# Kasli-SOC_power-controller.net
KiCad netlist of a schematic drawn in Altium Designer
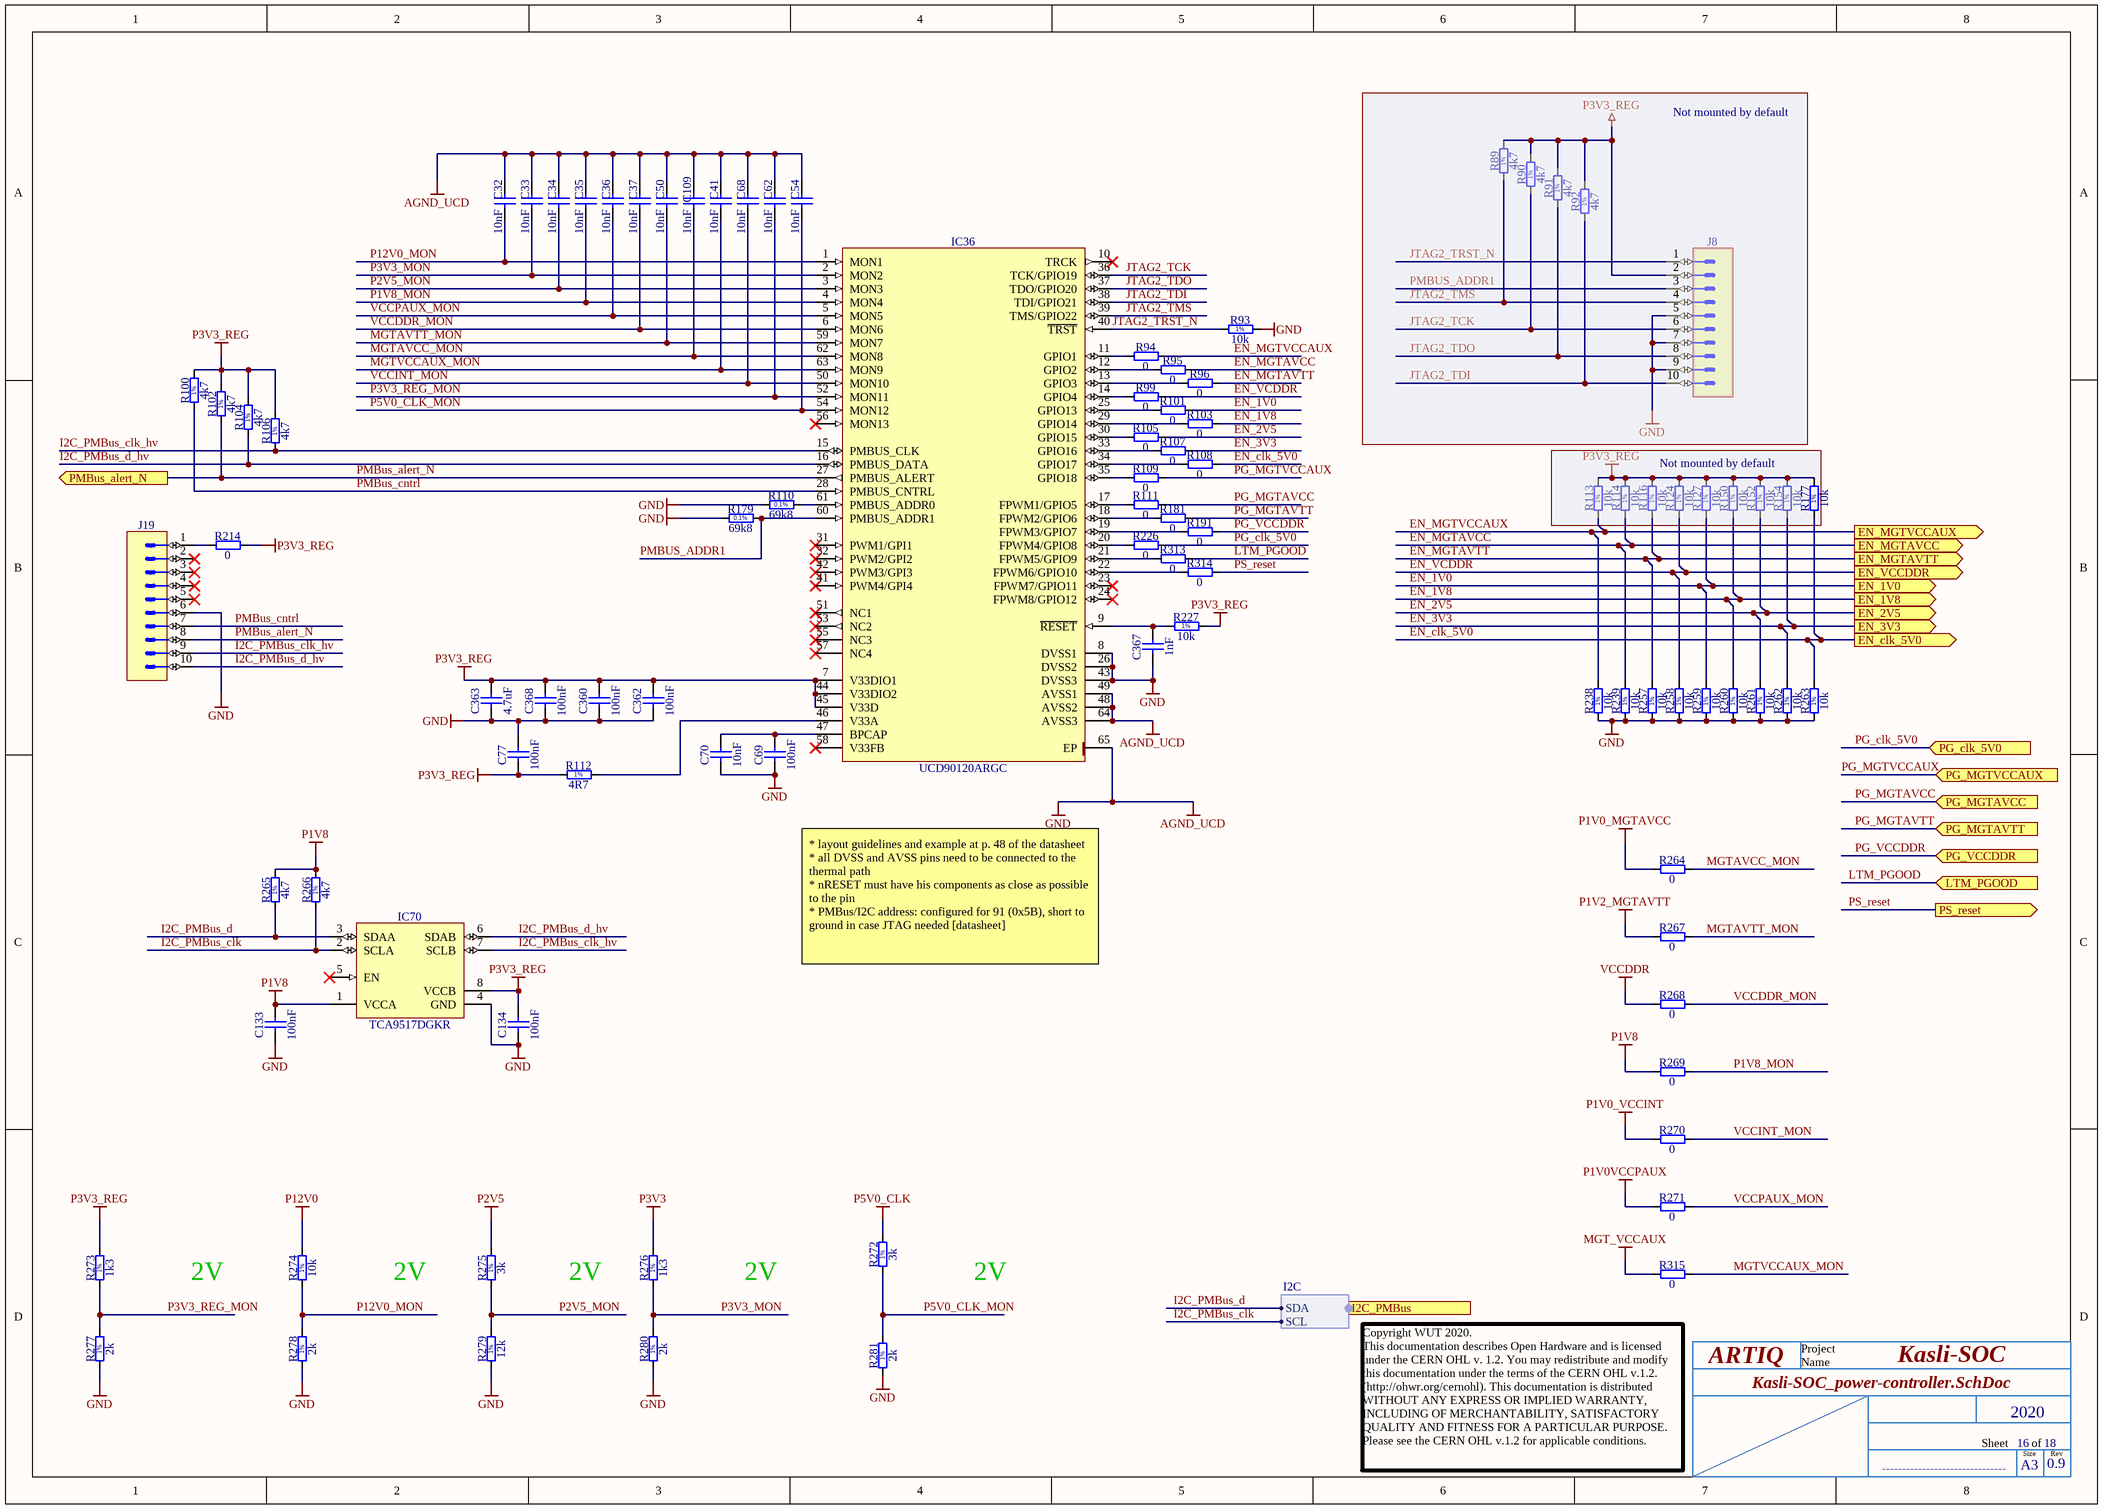
[diagram p0: Kasli-SOC_power-controller.SchDoc]

(export (version "E")
  (design (tool "Eeschema 10.0.6"))
  (components
    (comp (ref "C32")
      (value "10nF")
      (footprint "CAPC1005X55N")
      (description "Non-polarised capacitor")
      (fields (field (name "PART NUMBER") "CC0402_10NF_25V_10%_X7R") (field (name "VOLTAGE") "25V"))
      (libsource (lib "Capacitors") (part "Capacitor - non polarized"))
    )
    (comp (ref "C33")
      (value "10nF")
      (footprint "CAPC1005X55N")
      (description "Non-polarised capacitor")
      (fields (field (name "PART NUMBER") "CC0402_10NF_25V_10%_X7R") (field (name "VOLTAGE") "25V"))
      (libsource (lib "Capacitors") (part "Capacitor - non polarized"))
    )
    (comp (ref "C34")
      (value "10nF")
      (footprint "CAPC1005X55N")
      (description "Non-polarised capacitor")
      (fields (field (name "PART NUMBER") "CC0402_10NF_25V_10%_X7R") (field (name "VOLTAGE") "25V"))
      (libsource (lib "Capacitors") (part "Capacitor - non polarized"))
    )
    (comp (ref "C35")
      (value "10nF")
      (footprint "CAPC1005X55N")
      (description "Non-polarised capacitor")
      (fields (field (name "PART NUMBER") "CC0402_10NF_25V_10%_X7R") (field (name "VOLTAGE") "25V"))
      (libsource (lib "Capacitors") (part "Capacitor - non polarized"))
    )
    (comp (ref "C36")
      (value "10nF")
      (footprint "CAPC1005X55N")
      (description "Non-polarised capacitor")
      (fields (field (name "PART NUMBER") "CC0402_10NF_25V_10%_X7R") (field (name "VOLTAGE") "25V"))
      (libsource (lib "Capacitors") (part "Capacitor - non polarized"))
    )
    (comp (ref "C37")
      (value "10nF")
      (footprint "CAPC1005X55N")
      (description "Non-polarised capacitor")
      (fields (field (name "PART NUMBER") "CC0402_10NF_25V_10%_X7R") (field (name "VOLTAGE") "25V"))
      (libsource (lib "Capacitors") (part "Capacitor - non polarized"))
    )
    (comp (ref "C41")
      (value "10nF")
      (footprint "CAPC1005X55N")
      (description "Non-polarised capacitor")
      (fields (field (name "PART NUMBER") "CC0402_10NF_25V_10%_X7R") (field (name "VOLTAGE") "25V"))
      (libsource (lib "Capacitors") (part "Capacitor - non polarized"))
    )
    (comp (ref "C50")
      (value "10nF")
      (footprint "CAPC1005X55N")
      (description "Non-polarised capacitor")
      (fields (field (name "PART NUMBER") "CC0402_10NF_25V_10%_X7R") (field (name "VOLTAGE") "25V"))
      (libsource (lib "Capacitors") (part "Capacitor - non polarized"))
    )
    (comp (ref "C54")
      (value "10nF")
      (footprint "CAPC1005X55N")
      (description "Non-polarised capacitor")
      (fields (field (name "PART NUMBER") "CC0402_10NF_25V_10%_X7R") (field (name "VOLTAGE") "25V"))
      (libsource (lib "Capacitors") (part "Capacitor - non polarized"))
    )
    (comp (ref "C62")
      (value "10nF")
      (footprint "CAPC1005X55N")
      (description "Non-polarised capacitor")
      (fields (field (name "PART NUMBER") "CC0402_10NF_25V_10%_X7R") (field (name "VOLTAGE") "25V"))
      (libsource (lib "Capacitors") (part "Capacitor - non polarized"))
    )
    (comp (ref "C68")
      (value "10nF")
      (footprint "CAPC1005X55N")
      (description "Non-polarised capacitor")
      (fields (field (name "PART NUMBER") "CC0402_10NF_25V_10%_X7R") (field (name "VOLTAGE") "25V"))
      (libsource (lib "Capacitors") (part "Capacitor - non polarized"))
    )
    (comp (ref "C69")
      (value "100nF")
      (footprint "CAPC1005X55N")
      (description "Non-polarised capacitor")
      (fields (field (name "PART NUMBER") "CC0402_100NF_16V_10%_X7R") (field (name "VOLTAGE") "16V"))
      (libsource (lib "Capacitors") (part "Capacitor - non polarized"))
    )
    (comp (ref "C70")
      (value "10nF")
      (footprint "CAPC1005X55N")
      (description "Non-polarised capacitor")
      (fields (field (name "PART NUMBER") "CC0402_10NF_25V_10%_X7R") (field (name "VOLTAGE") "25V"))
      (libsource (lib "Capacitors") (part "Capacitor - non polarized"))
    )
    (comp (ref "C77")
      (value "100nF")
      (footprint "CAPC1005X55N")
      (description "Non-polarised capacitor")
      (fields (field (name "PART NUMBER") "CC0402_100NF_16V_10%_X7R") (field (name "VOLTAGE") "16V"))
      (libsource (lib "Capacitors") (part "Capacitor - non polarized"))
    )
    (comp (ref "C109")
      (value "10nF")
      (footprint "CAPC1005X55N")
      (description "Non-polarised capacitor")
      (fields (field (name "PART NUMBER") "CC0402_10NF_25V_10%_X7R") (field (name "VOLTAGE") "25V"))
      (libsource (lib "Capacitors") (part "Capacitor - non polarized"))
    )
    (comp (ref "C133")
      (value "100nF")
      (footprint "CAPC1005X55N")
      (description "Non-polarised capacitor")
      (fields (field (name "PART NUMBER") "CC0402_100NF_16V_10%_X7R") (field (name "VOLTAGE") "16V"))
      (libsource (lib "Capacitors") (part "Capacitor - non polarized"))
    )
    (comp (ref "C134")
      (value "100nF")
      (footprint "CAPC1005X55N")
      (description "Non-polarised capacitor")
      (fields (field (name "PART NUMBER") "CC0402_100NF_16V_10%_X7R") (field (name "VOLTAGE") "16V"))
      (libsource (lib "Capacitors") (part "Capacitor - non polarized"))
    )
    (comp (ref "C360")
      (value "100nF")
      (footprint "CAPC1005X55N")
      (description "Non-polarised capacitor")
      (fields (field (name "PART NUMBER") "CC0402_100NF_16V_10%_X7R") (field (name "VOLTAGE") "16V"))
      (libsource (lib "Capacitors") (part "Capacitor - non polarized"))
    )
    (comp (ref "C362")
      (value "100nF")
      (footprint "CAPC1005X55N")
      (description "Non-polarised capacitor")
      (fields (field (name "PART NUMBER") "CC0402_100NF_16V_10%_X7R") (field (name "VOLTAGE") "16V"))
      (libsource (lib "Capacitors") (part "Capacitor - non polarized"))
    )
    (comp (ref "C363")
      (value "4.7uF")
      (footprint "CAPC1005X55N")
      (description "Non-polarised capacitor")
      (fields (field (name "PART NUMBER") "CC0402_4.7UF_6.3V_20%_X5R") (field (name "VOLTAGE") "6.3V"))
      (libsource (lib "Capacitors") (part "Capacitor - non polarized"))
    )
    (comp (ref "C367")
      (value "1nF")
      (footprint "CAPC1005X55N")
      (description "Non-polarised capacitor")
      (fields (field (name "PART NUMBER") "CC0402_1NF_50V_10%_X7R") (field (name "VOLTAGE") "50V"))
      (libsource (lib "Capacitors") (part "Capacitor - non polarized"))
    )
    (comp (ref "C368")
      (value "100nF")
      (footprint "CAPC1005X55N")
      (description "Non-polarised capacitor")
      (fields (field (name "PART NUMBER") "CC0402_100NF_16V_10%_X7R") (field (name "VOLTAGE") "16V"))
      (libsource (lib "Capacitors") (part "Capacitor - non polarized"))
    )
    (comp (ref "IC36")
      (value "UCD90120ARGC")
      (footprint "QFN50P900X900X100-65N-S425")
      (description "12-Rail Power Supply Sequencer and Monitor")
      (fields (field (name "MANUFACTURER") "TEXAS INSTRUMENTS"))
      (libsource (lib "ICs And Semiconductors") (part "UCD90120ARGC"))
    )
    (comp (ref "IC70")
      (value "TCA9517DGKR")
      (footprint "SOP65P490X110-8N")
      (description "Level-Translating I2C Bus Repeater")
      (fields (field (name "MANUFACTURER") "TEXAS INSTRUMENTS"))
      (libsource (lib "ICs And Semiconductors") (part "TCA9517"))
    )
    (comp (ref "J8")
      (value "AMPMODU")
      (footprint "TYCO_1241050-5")
      (description "Connector 10 Male")
      (fields (field (name "PART NUMBER") "TYCO_1241050-5") (field (name "MANUFACTURER") "TYCO ELECTRONICS"))
      (libsource (lib "Connectors") (part "Connector 10 Male"))
    )
    (comp (ref "J19")
      (value "AMPMODU")
      (footprint "TYCO_1241050-5")
      (description "Connector 10 Male")
      (fields (field (name "PART NUMBER") "TYCO_1241050-5") (field (name "MANUFACTURER") "TYCO ELECTRONICS"))
      (libsource (lib "") (part "Connector 10 Male_1"))
    )
    (comp (ref "R89")
      (value "4k7")
      (footprint "RESC1005X40N")
      (description "Resistor - 1%")
      (fields (field (name "PART NUMBER") "R0402_4K7_1%_0.0625W_100PPM") (field (name "POWER") "0.0625W"))
      (libsource (lib "Resistors") (part "Resistor - 1%"))
    )
    (comp (ref "R90")
      (value "4k7")
      (footprint "RESC1005X40N")
      (description "Resistor - 1%")
      (fields (field (name "PART NUMBER") "R0402_4K7_1%_0.0625W_100PPM") (field (name "POWER") "0.0625W"))
      (libsource (lib "Resistors") (part "Resistor - 1%"))
    )
    (comp (ref "R91")
      (value "4k7")
      (footprint "RESC1005X40N")
      (description "Resistor - 1%")
      (fields (field (name "PART NUMBER") "R0402_4K7_1%_0.0625W_100PPM") (field (name "POWER") "0.0625W"))
      (libsource (lib "Resistors") (part "Resistor - 1%"))
    )
    (comp (ref "R92")
      (value "4k7")
      (footprint "RESC1005X40N")
      (description "Resistor - 1%")
      (fields (field (name "PART NUMBER") "R0402_4K7_1%_0.0625W_100PPM") (field (name "POWER") "0.0625W"))
      (libsource (lib "Resistors") (part "Resistor - 1%"))
    )
    (comp (ref "R93")
      (value "10k")
      (footprint "RESC1005X40N")
      (description "Resistor - 1%")
      (fields (field (name "PART NUMBER") "R0402_10K_1%_0.0625W_100PPM") (field (name "POWER") "0.0625W"))
      (libsource (lib "Resistors") (part "Resistor - 1%"))
    )
    (comp (ref "R94")
      (value "0")
      (footprint "RESC1005X40N")
      (description "Resistor")
      (fields (field (name "PART NUMBER") "R0402_0R_JUMPER") (field (name "MANUFACTURER") "GENERIC"))
      (libsource (lib "Resistors") (part "Resistor"))
    )
    (comp (ref "R95")
      (value "0")
      (footprint "RESC1005X40N")
      (description "Resistor")
      (fields (field (name "PART NUMBER") "R0402_0R_JUMPER") (field (name "MANUFACTURER") "GENERIC"))
      (libsource (lib "Resistors") (part "Resistor"))
    )
    (comp (ref "R96")
      (value "0")
      (footprint "RESC1005X40N")
      (description "Resistor")
      (fields (field (name "PART NUMBER") "R0402_0R_JUMPER") (field (name "MANUFACTURER") "GENERIC"))
      (libsource (lib "Resistors") (part "Resistor"))
    )
    (comp (ref "R99")
      (value "0")
      (footprint "RESC1005X40N")
      (description "Resistor")
      (fields (field (name "PART NUMBER") "R0402_0R_JUMPER") (field (name "MANUFACTURER") "GENERIC"))
      (libsource (lib "Resistors") (part "Resistor"))
    )
    (comp (ref "R100")
      (value "4k7")
      (footprint "RESC1005X40N")
      (description "Resistor - 1%")
      (fields (field (name "PART NUMBER") "R0402_4K7_1%_0.0625W_100PPM") (field (name "POWER") "0.0625W"))
      (libsource (lib "Resistors") (part "Resistor - 1%"))
    )
    (comp (ref "R101")
      (value "0")
      (footprint "RESC1005X40N")
      (description "Resistor")
      (fields (field (name "PART NUMBER") "R0402_0R_JUMPER") (field (name "MANUFACTURER") "GENERIC"))
      (libsource (lib "Resistors") (part "Resistor"))
    )
    (comp (ref "R102")
      (value "4k7")
      (footprint "RESC1005X40N")
      (description "Resistor - 1%")
      (fields (field (name "PART NUMBER") "R0402_4K7_1%_0.0625W_100PPM") (field (name "POWER") "0.0625W"))
      (libsource (lib "Resistors") (part "Resistor - 1%"))
    )
    (comp (ref "R103")
      (value "0")
      (footprint "RESC1005X40N")
      (description "Resistor")
      (fields (field (name "PART NUMBER") "R0402_0R_JUMPER") (field (name "MANUFACTURER") "GENERIC"))
      (libsource (lib "Resistors") (part "Resistor"))
    )
    (comp (ref "R104")
      (value "4k7")
      (footprint "RESC1005X40N")
      (description "Resistor - 1%")
      (fields (field (name "PART NUMBER") "R0402_4K7_1%_0.0625W_100PPM") (field (name "POWER") "0.0625W"))
      (libsource (lib "Resistors") (part "Resistor - 1%"))
    )
    (comp (ref "R105")
      (value "0")
      (footprint "RESC1005X40N")
      (description "Resistor")
      (fields (field (name "PART NUMBER") "R0402_0R_JUMPER") (field (name "MANUFACTURER") "GENERIC"))
      (libsource (lib "Resistors") (part "Resistor"))
    )
    (comp (ref "R106")
      (value "4k7")
      (footprint "RESC1005X40N")
      (description "Resistor - 1%")
      (fields (field (name "PART NUMBER") "R0402_4K7_1%_0.0625W_100PPM") (field (name "POWER") "0.0625W"))
      (libsource (lib "Resistors") (part "Resistor - 1%"))
    )
    (comp (ref "R107")
      (value "0")
      (footprint "RESC1005X40N")
      (description "Resistor")
      (fields (field (name "PART NUMBER") "R0402_0R_JUMPER") (field (name "MANUFACTURER") "GENERIC"))
      (libsource (lib "Resistors") (part "Resistor"))
    )
    (comp (ref "R108")
      (value "0")
      (footprint "RESC1005X40N")
      (description "Resistor")
      (fields (field (name "PART NUMBER") "R0402_0R_JUMPER") (field (name "MANUFACTURER") "GENERIC"))
      (libsource (lib "Resistors") (part "Resistor"))
    )
    (comp (ref "R109")
      (value "0")
      (footprint "RESC1005X40N")
      (description "Resistor")
      (fields (field (name "PART NUMBER") "R0402_0R_JUMPER") (field (name "MANUFACTURER") "GENERIC"))
      (libsource (lib "Resistors") (part "Resistor"))
    )
    (comp (ref "R110")
      (value "69k8")
      (footprint "RESC1608X55N")
      (description "Resistor - 0.1%")
      (fields (field (name "PART NUMBER") "R0603_69K8_0.1%_0.063W_10PPM") (field (name "POWER") "0.063W"))
      (libsource (lib "Resistors") (part "Resistor - 0.1%"))
    )
    (comp (ref "R111")
      (value "0")
      (footprint "RESC1005X40N")
      (description "Resistor")
      (fields (field (name "PART NUMBER") "R0402_0R_JUMPER") (field (name "MANUFACTURER") "GENERIC"))
      (libsource (lib "Resistors") (part "Resistor"))
    )
    (comp (ref "R112")
      (value "4R7")
      (footprint "RESC2012X60N")
      (description "Resistor - 1%")
      (fields (field (name "PART NUMBER") "R0805_4R7_1%_0.125W_200PPM") (field (name "POWER") "0.125W"))
      (libsource (lib "Resistors") (part "Resistor - 1%"))
    )
    (comp (ref "R113")
      (value "10k")
      (footprint "RESC1005X40N")
      (description "Resistor - 1%")
      (fields (field (name "PART NUMBER") "R0402_10K_1%_0.0625W_100PPM") (field (name "POWER") "0.0625W"))
      (libsource (lib "Resistors") (part "Resistor - 1%"))
    )
    (comp (ref "R114")
      (value "10k")
      (footprint "RESC1005X40N")
      (description "Resistor - 1%")
      (fields (field (name "PART NUMBER") "R0402_10K_1%_0.0625W_100PPM") (field (name "POWER") "0.0625W"))
      (libsource (lib "Resistors") (part "Resistor - 1%"))
    )
    (comp (ref "R116")
      (value "10k")
      (footprint "RESC1005X40N")
      (description "Resistor - 1%")
      (fields (field (name "PART NUMBER") "R0402_10K_1%_0.0625W_100PPM") (field (name "POWER") "0.0625W"))
      (libsource (lib "Resistors") (part "Resistor - 1%"))
    )
    (comp (ref "R124")
      (value "10k")
      (footprint "RESC1005X40N")
      (description "Resistor - 1%")
      (fields (field (name "PART NUMBER") "R0402_10K_1%_0.0625W_100PPM") (field (name "POWER") "0.0625W"))
      (libsource (lib "Resistors") (part "Resistor - 1%"))
    )
    (comp (ref "R127")
      (value "10k")
      (footprint "RESC1005X40N")
      (description "Resistor - 1%")
      (fields (field (name "PART NUMBER") "R0402_10K_1%_0.0625W_100PPM") (field (name "POWER") "0.0625W"))
      (libsource (lib "Resistors") (part "Resistor - 1%"))
    )
    (comp (ref "R150")
      (value "10k")
      (footprint "RESC1005X40N")
      (description "Resistor - 1%")
      (fields (field (name "PART NUMBER") "R0402_10K_1%_0.0625W_100PPM") (field (name "POWER") "0.0625W"))
      (libsource (lib "Resistors") (part "Resistor - 1%"))
    )
    (comp (ref "R152")
      (value "10k")
      (footprint "RESC1005X40N")
      (description "Resistor - 1%")
      (fields (field (name "PART NUMBER") "R0402_10K_1%_0.0625W_100PPM") (field (name "POWER") "0.0625W"))
      (libsource (lib "Resistors") (part "Resistor - 1%"))
    )
    (comp (ref "R154")
      (value "10k")
      (footprint "RESC1005X40N")
      (description "Resistor - 1%")
      (fields (field (name "PART NUMBER") "R0402_10K_1%_0.0625W_100PPM") (field (name "POWER") "0.0625W"))
      (libsource (lib "Resistors") (part "Resistor - 1%"))
    )
    (comp (ref "R177")
      (value "10k")
      (footprint "RESC1005X40N")
      (description "Resistor - 1%")
      (fields (field (name "PART NUMBER") "R0402_10K_1%_0.0625W_100PPM") (field (name "POWER") "0.0625W"))
      (libsource (lib "Resistors") (part "Resistor - 1%"))
    )
    (comp (ref "R179")
      (value "69k8")
      (footprint "RESC1608X55N")
      (description "Resistor - 0.1%")
      (fields (field (name "PART NUMBER") "R0603_69K8_0.1%_0.063W_10PPM") (field (name "POWER") "0.063W"))
      (libsource (lib "Resistors") (part "Resistor - 0.1%"))
    )
    (comp (ref "R181")
      (value "0")
      (footprint "RESC1005X40N")
      (description "Resistor")
      (fields (field (name "PART NUMBER") "R0402_0R_JUMPER") (field (name "MANUFACTURER") "GENERIC"))
      (libsource (lib "Resistors") (part "Resistor"))
    )
    (comp (ref "R191")
      (value "0")
      (footprint "RESC1005X40N")
      (description "Resistor")
      (fields (field (name "PART NUMBER") "R0402_0R_JUMPER") (field (name "MANUFACTURER") "GENERIC"))
      (libsource (lib "Resistors") (part "Resistor"))
    )
    (comp (ref "R214")
      (value "0")
      (footprint "RESC1005X40N")
      (description "Resistor")
      (fields (field (name "PART NUMBER") "R0402_0R_JUMPER") (field (name "MANUFACTURER") "GENERIC"))
      (libsource (lib "Resistors") (part "Resistor"))
    )
    (comp (ref "R226")
      (value "0")
      (footprint "RESC1005X40N")
      (description "Resistor")
      (fields (field (name "PART NUMBER") "R0402_0R_JUMPER") (field (name "MANUFACTURER") "GENERIC"))
      (libsource (lib "Resistors") (part "Resistor"))
    )
    (comp (ref "R227")
      (value "10k")
      (footprint "RESC1005X40N")
      (description "Resistor - 1%")
      (fields (field (name "PART NUMBER") "R0402_10K_1%_0.0625W_100PPM") (field (name "POWER") "0.0625W"))
      (libsource (lib "Resistors") (part "Resistor - 1%"))
    )
    (comp (ref "R238")
      (value "10k")
      (footprint "RESC1005X40N")
      (description "Resistor - 1%")
      (fields (field (name "PART NUMBER") "R0402_10K_1%_0.0625W_100PPM") (field (name "POWER") "0.0625W"))
      (libsource (lib "Resistors") (part "Resistor - 1%"))
    )
    (comp (ref "R239")
      (value "10k")
      (footprint "RESC1005X40N")
      (description "Resistor - 1%")
      (fields (field (name "PART NUMBER") "R0402_10K_1%_0.0625W_100PPM") (field (name "POWER") "0.0625W"))
      (libsource (lib "Resistors") (part "Resistor - 1%"))
    )
    (comp (ref "R257")
      (value "10k")
      (footprint "RESC1005X40N")
      (description "Resistor - 1%")
      (fields (field (name "PART NUMBER") "R0402_10K_1%_0.0625W_100PPM") (field (name "POWER") "0.0625W"))
      (libsource (lib "Resistors") (part "Resistor - 1%"))
    )
    (comp (ref "R258")
      (value "10k")
      (footprint "RESC1005X40N")
      (description "Resistor - 1%")
      (fields (field (name "PART NUMBER") "R0402_10K_1%_0.0625W_100PPM") (field (name "POWER") "0.0625W"))
      (libsource (lib "Resistors") (part "Resistor - 1%"))
    )
    (comp (ref "R259")
      (value "10k")
      (footprint "RESC1005X40N")
      (description "Resistor - 1%")
      (fields (field (name "PART NUMBER") "R0402_10K_1%_0.0625W_100PPM") (field (name "POWER") "0.0625W"))
      (libsource (lib "Resistors") (part "Resistor - 1%"))
    )
    (comp (ref "R260")
      (value "10k")
      (footprint "RESC1005X40N")
      (description "Resistor - 1%")
      (fields (field (name "PART NUMBER") "R0402_10K_1%_0.0625W_100PPM") (field (name "POWER") "0.0625W"))
      (libsource (lib "Resistors") (part "Resistor - 1%"))
    )
    (comp (ref "R261")
      (value "10k")
      (footprint "RESC1005X40N")
      (description "Resistor - 1%")
      (fields (field (name "PART NUMBER") "R0402_10K_1%_0.0625W_100PPM") (field (name "POWER") "0.0625W"))
      (libsource (lib "Resistors") (part "Resistor - 1%"))
    )
    (comp (ref "R262")
      (value "10k")
      (footprint "RESC1005X40N")
      (description "Resistor - 1%")
      (fields (field (name "PART NUMBER") "R0402_10K_1%_0.0625W_100PPM") (field (name "POWER") "0.0625W"))
      (libsource (lib "Resistors") (part "Resistor - 1%"))
    )
    (comp (ref "R263")
      (value "10k")
      (footprint "RESC1005X40N")
      (description "Resistor - 1%")
      (fields (field (name "PART NUMBER") "R0402_10K_1%_0.0625W_100PPM") (field (name "POWER") "0.0625W"))
      (libsource (lib "Resistors") (part "Resistor - 1%"))
    )
    (comp (ref "R264")
      (value "0")
      (footprint "RESC1005X40N")
      (description "Resistor")
      (fields (field (name "PART NUMBER") "R0402_0R_JUMPER") (field (name "MANUFACTURER") "GENERIC"))
      (libsource (lib "Resistors") (part "Resistor"))
    )
    (comp (ref "R265")
      (value "4k7")
      (footprint "RESC2012X60N")
      (description "Resistor - 1%")
      (fields (field (name "PART NUMBER") "R0805_4K7_1%_0.125W_100PPM") (field (name "POWER") "0.125W"))
      (libsource (lib "Resistors") (part "Resistor - 1%"))
    )
    (comp (ref "R266")
      (value "4k7")
      (footprint "RESC2012X60N")
      (description "Resistor - 1%")
      (fields (field (name "PART NUMBER") "R0805_4K7_1%_0.125W_100PPM") (field (name "POWER") "0.125W"))
      (libsource (lib "Resistors") (part "Resistor - 1%"))
    )
    (comp (ref "R267")
      (value "0")
      (footprint "RESC1005X40N")
      (description "Resistor")
      (fields (field (name "PART NUMBER") "R0402_0R_JUMPER") (field (name "MANUFACTURER") "GENERIC"))
      (libsource (lib "Resistors") (part "Resistor"))
    )
    (comp (ref "R268")
      (value "0")
      (footprint "RESC1005X40N")
      (description "Resistor")
      (fields (field (name "PART NUMBER") "R0402_0R_JUMPER") (field (name "MANUFACTURER") "GENERIC"))
      (libsource (lib "Resistors") (part "Resistor"))
    )
    (comp (ref "R269")
      (value "0")
      (footprint "RESC1005X40N")
      (description "Resistor")
      (fields (field (name "PART NUMBER") "R0402_0R_JUMPER") (field (name "MANUFACTURER") "GENERIC"))
      (libsource (lib "Resistors") (part "Resistor"))
    )
    (comp (ref "R270")
      (value "0")
      (footprint "RESC1005X40N")
      (description "Resistor")
      (fields (field (name "PART NUMBER") "R0402_0R_JUMPER") (field (name "MANUFACTURER") "GENERIC"))
      (libsource (lib "Resistors") (part "Resistor"))
    )
    (comp (ref "R271")
      (value "0")
      (footprint "RESC1005X40N")
      (description "Resistor")
      (fields (field (name "PART NUMBER") "R0402_0R_JUMPER") (field (name "MANUFACTURER") "GENERIC"))
      (libsource (lib "Resistors") (part "Resistor"))
    )
    (comp (ref "R272")
      (value "3k")
      (footprint "RESC1005X40N")
      (description "Resistor - 1%")
      (fields (field (name "PART NUMBER") "R0402_3K_1%_0.0625W_100PPM") (field (name "POWER") "0.0625W"))
      (libsource (lib "Resistors") (part "Resistor - 1%"))
    )
    (comp (ref "R273")
      (value "1k3")
      (footprint "RESC1005X40N")
      (description "Resistor - 1%")
      (fields (field (name "PART NUMBER") "R0402_1K3_1%_0.0625W_100PPM") (field (name "POWER") "0.0625W"))
      (libsource (lib "Resistors") (part "Resistor - 1%"))
    )
    (comp (ref "R274")
      (value "10k")
      (footprint "RESC1005X40N")
      (description "Resistor - 1%")
      (fields (field (name "PART NUMBER") "R0402_10K_1%_0.0625W_100PPM") (field (name "POWER") "0.0625W"))
      (libsource (lib "Resistors") (part "Resistor - 1%"))
    )
    (comp (ref "R275")
      (value "3k")
      (footprint "RESC1005X40N")
      (description "Resistor - 1%")
      (fields (field (name "PART NUMBER") "R0402_3K_1%_0.0625W_100PPM") (field (name "POWER") "0.0625W"))
      (libsource (lib "Resistors") (part "Resistor - 1%"))
    )
    (comp (ref "R276")
      (value "1k3")
      (footprint "RESC1005X40N")
      (description "Resistor - 1%")
      (fields (field (name "PART NUMBER") "R0402_1K3_1%_0.0625W_100PPM") (field (name "POWER") "0.0625W"))
      (libsource (lib "Resistors") (part "Resistor - 1%"))
    )
    (comp (ref "R277")
      (value "2k")
      (footprint "RESC1005X40N")
      (description "Resistor - 1%")
      (fields (field (name "PART NUMBER") "R0402_2K_1%_0.0625W_100PPM") (field (name "POWER") "0.0625W"))
      (libsource (lib "Resistors") (part "Resistor - 1%"))
    )
    (comp (ref "R278")
      (value "2k")
      (footprint "RESC1005X40N")
      (description "Resistor - 1%")
      (fields (field (name "PART NUMBER") "R0402_2K_1%_0.0625W_100PPM") (field (name "POWER") "0.0625W"))
      (libsource (lib "Resistors") (part "Resistor - 1%"))
    )
    (comp (ref "R279")
      (value "12k")
      (footprint "RESC1005X40N")
      (description "Resistor - 1%")
      (fields (field (name "PART NUMBER") "R0402_12K_1%_0.0625W_100PPM") (field (name "POWER") "0.0625W"))
      (libsource (lib "Resistors") (part "Resistor - 1%"))
    )
    (comp (ref "R280")
      (value "2k")
      (footprint "RESC1005X40N")
      (description "Resistor - 1%")
      (fields (field (name "PART NUMBER") "R0402_2K_1%_0.0625W_100PPM") (field (name "POWER") "0.0625W"))
      (libsource (lib "Resistors") (part "Resistor - 1%"))
    )
    (comp (ref "R281")
      (value "2k")
      (footprint "RESC1005X40N")
      (description "Resistor - 1%")
      (fields (field (name "PART NUMBER") "R0402_2K_1%_0.0625W_100PPM") (field (name "POWER") "0.0625W"))
      (libsource (lib "Resistors") (part "Resistor - 1%"))
    )
    (comp (ref "R313")
      (value "0")
      (footprint "RESC1005X40N")
      (description "Resistor")
      (fields (field (name "PART NUMBER") "R0402_0R_JUMPER") (field (name "MANUFACTURER") "GENERIC"))
      (libsource (lib "Resistors") (part "Resistor"))
    )
    (comp (ref "R314")
      (value "0")
      (footprint "RESC1005X40N")
      (description "Resistor")
      (fields (field (name "PART NUMBER") "R0402_0R_JUMPER") (field (name "MANUFACTURER") "GENERIC"))
      (libsource (lib "Resistors") (part "Resistor"))
    )
    (comp (ref "R315")
      (value "0")
      (footprint "RESC1005X40N")
      (description "Resistor")
      (fields (field (name "PART NUMBER") "R0402_0R_JUMPER") (field (name "MANUFACTURER") "GENERIC"))
      (libsource (lib "Resistors") (part "Resistor"))
    )
  )
  (nets
    (net (code "2") (name "/EN_1V0") (class "Default")
      (node (ref "R101") (pin "2") (pinfunction "2_2") (pintype "passive"))
      (node (ref "R127") (pin "1") (pinfunction "1_1") (pintype "passive"))
      (node (ref "R259") (pin "2") (pinfunction "2_2") (pintype "passive"))
    )
    (net (code "3") (name "/EN_1V8") (class "Default")
      (node (ref "R103") (pin "2") (pinfunction "2_2") (pintype "passive"))
      (node (ref "R150") (pin "1") (pinfunction "1_1") (pintype "passive"))
      (node (ref "R260") (pin "2") (pinfunction "2_2") (pintype "passive"))
    )
    (net (code "4") (name "/EN_2V5") (class "Default")
      (node (ref "R105") (pin "2") (pinfunction "2_2") (pintype "passive"))
      (node (ref "R152") (pin "1") (pinfunction "1_1") (pintype "passive"))
      (node (ref "R261") (pin "2") (pinfunction "2_2") (pintype "passive"))
    )
    (net (code "5") (name "/EN_3V3") (class "Default")
      (node (ref "R107") (pin "2") (pinfunction "2_2") (pintype "passive"))
      (node (ref "R154") (pin "1") (pinfunction "1_1") (pintype "passive"))
      (node (ref "R262") (pin "2") (pinfunction "2_2") (pintype "passive"))
    )
    (net (code "6") (name "/EN_MGTAVCC") (class "Default")
      (node (ref "R114") (pin "1") (pinfunction "1_1") (pintype "passive"))
      (node (ref "R239") (pin "2") (pinfunction "2_2") (pintype "passive"))
      (node (ref "R95") (pin "2") (pinfunction "2_2") (pintype "passive"))
    )
    (net (code "7") (name "/EN_MGTAVTT") (class "Default")
      (node (ref "R116") (pin "1") (pinfunction "1_1") (pintype "passive"))
      (node (ref "R257") (pin "2") (pinfunction "2_2") (pintype "passive"))
      (node (ref "R96") (pin "2") (pinfunction "2_2") (pintype "passive"))
    )
    (net (code "8") (name "/EN_MGTVCCAUX") (class "Default")
      (node (ref "R113") (pin "1") (pinfunction "1_1") (pintype "passive"))
      (node (ref "R238") (pin "2") (pinfunction "2_2") (pintype "passive"))
      (node (ref "R94") (pin "2") (pinfunction "2_2") (pintype "passive"))
    )
    (net (code "9") (name "/EN_VCDDR") (class "Default")
      (node (ref "R124") (pin "1") (pinfunction "1_1") (pintype "passive"))
      (node (ref "R258") (pin "2") (pinfunction "2_2") (pintype "passive"))
      (node (ref "R99") (pin "2") (pinfunction "2_2") (pintype "passive"))
    )
    (net (code "10") (name "/EN_clk_5V0") (class "Default")
      (node (ref "R108") (pin "2") (pinfunction "2_2") (pintype "passive"))
      (node (ref "R177") (pin "1") (pinfunction "1_1") (pintype "passive"))
      (node (ref "R263") (pin "2") (pinfunction "2_2") (pintype "passive"))
    )
    (net (code "11") (name "/I2C_PMBus_clk") (class "Default")
      (node (ref "IC70") (pin "2") (pinfunction "SCLA_2") (pintype "bidirectional"))
      (node (ref "R266") (pin "1") (pinfunction "1_1") (pintype "passive"))
    )
    (net (code "12") (name "/I2C_PMBus_clk_hv") (class "Default")
      (node (ref "IC36") (pin "15") (pinfunction "PMBUS_CLK_15") (pintype "bidirectional"))
      (node (ref "IC70") (pin "7") (pinfunction "SCLB_7") (pintype "bidirectional"))
      (node (ref "J19") (pin "9") (pinfunction "9_9") (pintype "bidirectional"))
      (node (ref "R106") (pin "1") (pinfunction "1_1") (pintype "passive"))
    )
    (net (code "13") (name "/I2C_PMBus_d") (class "Default")
      (node (ref "IC70") (pin "3") (pinfunction "SDAA_3") (pintype "bidirectional"))
      (node (ref "R265") (pin "1") (pinfunction "1_1") (pintype "passive"))
    )
    (net (code "14") (name "/I2C_PMBus_d_hv") (class "Default")
      (node (ref "IC36") (pin "16") (pinfunction "PMBUS_DATA_16") (pintype "bidirectional"))
      (node (ref "IC70") (pin "6") (pinfunction "SDAB_6") (pintype "bidirectional"))
      (node (ref "J19") (pin "10") (pinfunction "10_10") (pintype "bidirectional"))
      (node (ref "R104") (pin "1") (pinfunction "1_1") (pintype "passive"))
    )
    (net (code "15") (name "/JTAG2_TCK") (class "Default")
      (node (ref "IC36") (pin "36") (pinfunction "TCK/GPIO19_36") (pintype "bidirectional"))
      (node (ref "J8") (pin "6") (pinfunction "6_6") (pintype "bidirectional"))
      (node (ref "R90") (pin "1") (pinfunction "1_1") (pintype "passive"))
    )
    (net (code "16") (name "/JTAG2_TDI") (class "Default")
      (node (ref "IC36") (pin "38") (pinfunction "TDI/GPIO21_38") (pintype "bidirectional"))
      (node (ref "J8") (pin "10") (pinfunction "10_10") (pintype "bidirectional"))
      (node (ref "R92") (pin "1") (pinfunction "1_1") (pintype "passive"))
    )
    (net (code "17") (name "/JTAG2_TDO") (class "Default")
      (node (ref "IC36") (pin "37") (pinfunction "TDO/GPIO20_37") (pintype "bidirectional"))
      (node (ref "J8") (pin "8") (pinfunction "8_8") (pintype "bidirectional"))
      (node (ref "R91") (pin "1") (pinfunction "1_1") (pintype "passive"))
    )
    (net (code "18") (name "/JTAG2_TMS") (class "Default")
      (node (ref "IC36") (pin "39") (pinfunction "TMS/GPIO22_39") (pintype "bidirectional"))
      (node (ref "J8") (pin "4") (pinfunction "4_4") (pintype "bidirectional"))
      (node (ref "R89") (pin "1") (pinfunction "1_1") (pintype "passive"))
    )
    (net (code "19") (name "/JTAG2_TRST_N") (class "Default")
      (node (ref "IC36") (pin "40") (pinfunction "~{TRST}_40") (pintype "input"))
      (node (ref "J8") (pin "1") (pinfunction "1_1") (pintype "bidirectional"))
      (node (ref "R93") (pin "1") (pinfunction "1_1") (pintype "passive"))
    )
    (net (code "20") (name "/LTM_PGOOD") (class "Default")
      (node (ref "R313") (pin "2") (pinfunction "2_2") (pintype "passive"))
    )
    (net (code "21") (name "/MGTAVCC_MON") (class "Default")
      (node (ref "C109") (pin "1") (pinfunction "1_1") (pintype "passive"))
      (node (ref "IC36") (pin "62") (pinfunction "MON8_62") (pintype "input"))
      (node (ref "R264") (pin "2") (pinfunction "2_2") (pintype "passive"))
    )
    (net (code "22") (name "/MGTAVTT_MON") (class "Default")
      (node (ref "C50") (pin "1") (pinfunction "1_1") (pintype "passive"))
      (node (ref "IC36") (pin "59") (pinfunction "MON7_59") (pintype "input"))
      (node (ref "R267") (pin "2") (pinfunction "2_2") (pintype "passive"))
    )
    (net (code "23") (name "/MGTVCCAUX_MON") (class "Default")
      (node (ref "C41") (pin "1") (pinfunction "1_1") (pintype "passive"))
      (node (ref "IC36") (pin "63") (pinfunction "MON9_63") (pintype "input"))
      (node (ref "R315") (pin "2") (pinfunction "2_2") (pintype "passive"))
    )
    (net (code "24") (name "/P1V8_MON") (class "Default")
      (node (ref "C35") (pin "1") (pinfunction "1_1") (pintype "passive"))
      (node (ref "IC36") (pin "4") (pinfunction "MON4_4") (pintype "input"))
      (node (ref "R269") (pin "2") (pinfunction "2_2") (pintype "passive"))
    )
    (net (code "25") (name "/P2V5_MON") (class "Default")
      (node (ref "C34") (pin "1") (pinfunction "1_1") (pintype "passive"))
      (node (ref "IC36") (pin "3") (pinfunction "MON3_3") (pintype "input"))
      (node (ref "R275") (pin "1") (pinfunction "1_1") (pintype "passive"))
      (node (ref "R279") (pin "2") (pinfunction "2_2") (pintype "passive"))
    )
    (net (code "26") (name "/P3V3_MON") (class "Default")
      (node (ref "C33") (pin "1") (pinfunction "1_1") (pintype "passive"))
      (node (ref "IC36") (pin "2") (pinfunction "MON2_2") (pintype "input"))
      (node (ref "R276") (pin "1") (pinfunction "1_1") (pintype "passive"))
      (node (ref "R280") (pin "2") (pinfunction "2_2") (pintype "passive"))
    )
    (net (code "27") (name "/P3V3_REG_MON") (class "Default")
      (node (ref "C62") (pin "1") (pinfunction "1_1") (pintype "passive"))
      (node (ref "IC36") (pin "52") (pinfunction "MON11_52") (pintype "input"))
      (node (ref "R273") (pin "1") (pinfunction "1_1") (pintype "passive"))
      (node (ref "R277") (pin "2") (pinfunction "2_2") (pintype "passive"))
    )
    (net (code "28") (name "/P5V0_CLK_MON") (class "Default")
      (node (ref "C54") (pin "1") (pinfunction "1_1") (pintype "passive"))
      (node (ref "IC36") (pin "54") (pinfunction "MON12_54") (pintype "input"))
      (node (ref "R272") (pin "1") (pinfunction "1_1") (pintype "passive"))
      (node (ref "R281") (pin "2") (pinfunction "2_2") (pintype "passive"))
    )
    (net (code "29") (name "/P12V0_MON") (class "Default")
      (node (ref "C32") (pin "1") (pinfunction "1_1") (pintype "passive"))
      (node (ref "IC36") (pin "1") (pinfunction "MON1_1") (pintype "input"))
      (node (ref "R274") (pin "1") (pinfunction "1_1") (pintype "passive"))
      (node (ref "R278") (pin "2") (pinfunction "2_2") (pintype "passive"))
    )
    (net (code "30") (name "/PG_MGTAVCC") (class "Default")
      (node (ref "R111") (pin "2") (pinfunction "2_2") (pintype "passive"))
    )
    (net (code "31") (name "/PG_MGTAVTT") (class "Default")
      (node (ref "R181") (pin "2") (pinfunction "2_2") (pintype "passive"))
    )
    (net (code "32") (name "/PG_MGTVCCAUX") (class "Default")
      (node (ref "R109") (pin "2") (pinfunction "2_2") (pintype "passive"))
    )
    (net (code "33") (name "/PG_VCCDDR") (class "Default")
      (node (ref "R191") (pin "2") (pinfunction "2_2") (pintype "passive"))
    )
    (net (code "34") (name "/PG_clk_5V0") (class "Default")
      (node (ref "R226") (pin "2") (pinfunction "2_2") (pintype "passive"))
    )
    (net (code "35") (name "/PMBUS_ADDR1") (class "Default")
      (node (ref "IC36") (pin "60") (pinfunction "PMBUS_ADDR1_60") (pintype "input"))
      (node (ref "J8") (pin "3") (pinfunction "3_3") (pintype "bidirectional"))
      (node (ref "R179") (pin "2") (pinfunction "2_2") (pintype "passive"))
    )
    (net (code "36") (name "/PMBus_alert_N") (class "Default")
      (node (ref "IC36") (pin "27") (pinfunction "PMBUS_ALERT_27") (pintype "output"))
      (node (ref "J19") (pin "8") (pinfunction "8_8") (pintype "bidirectional"))
      (node (ref "R102") (pin "1") (pinfunction "1_1") (pintype "passive"))
    )
    (net (code "37") (name "/PMBus_cntrl") (class "Default")
      (node (ref "IC36") (pin "28") (pinfunction "PMBUS_CNTRL_28") (pintype "input"))
      (node (ref "J19") (pin "7") (pinfunction "7_7") (pintype "bidirectional"))
      (node (ref "R100") (pin "1") (pinfunction "1_1") (pintype "passive"))
    )
    (net (code "38") (name "/PS_reset") (class "Default")
      (node (ref "R314") (pin "2") (pinfunction "2_2") (pintype "passive"))
    )
    (net (code "39") (name "/VCCDDR_MON") (class "Default")
      (node (ref "C37") (pin "1") (pinfunction "1_1") (pintype "passive"))
      (node (ref "IC36") (pin "6") (pinfunction "MON6_6") (pintype "input"))
      (node (ref "R268") (pin "2") (pinfunction "2_2") (pintype "passive"))
    )
    (net (code "40") (name "/VCCINT_MON") (class "Default")
      (node (ref "C68") (pin "1") (pinfunction "1_1") (pintype "passive"))
      (node (ref "IC36") (pin "50") (pinfunction "MON10_50") (pintype "input"))
      (node (ref "R270") (pin "2") (pinfunction "2_2") (pintype "passive"))
    )
    (net (code "41") (name "/VCCPAUX_MON") (class "Default")
      (node (ref "C36") (pin "1") (pinfunction "1_1") (pintype "passive"))
      (node (ref "IC36") (pin "5") (pinfunction "MON5_5") (pintype "input"))
      (node (ref "R271") (pin "2") (pinfunction "2_2") (pintype "passive"))
    )
    (net (code "43") (name "AGND_UCD") (class "Default")
      (node (ref "C109") (pin "2") (pinfunction "2_2") (pintype "passive"))
      (node (ref "C133") (pin "1") (pinfunction "1_1") (pintype "passive"))
      (node (ref "C134") (pin "1") (pinfunction "1_1") (pintype "passive"))
      (node (ref "C32") (pin "2") (pinfunction "2_2") (pintype "passive"))
      (node (ref "C33") (pin "2") (pinfunction "2_2") (pintype "passive"))
      (node (ref "C34") (pin "2") (pinfunction "2_2") (pintype "passive"))
      (node (ref "C35") (pin "2") (pinfunction "2_2") (pintype "passive"))
      (node (ref "C36") (pin "2") (pinfunction "2_2") (pintype "passive"))
      (node (ref "C360") (pin "1") (pinfunction "1_1") (pintype "passive"))
      (node (ref "C362") (pin "1") (pinfunction "1_1") (pintype "passive"))
      (node (ref "C363") (pin "1") (pinfunction "1_1") (pintype "passive"))
      (node (ref "C367") (pin "1") (pinfunction "1_1") (pintype "passive"))
      (node (ref "C368") (pin "1") (pinfunction "1_1") (pintype "passive"))
      (node (ref "C37") (pin "2") (pinfunction "2_2") (pintype "passive"))
      (node (ref "C41") (pin "2") (pinfunction "2_2") (pintype "passive"))
      (node (ref "C50") (pin "2") (pinfunction "2_2") (pintype "passive"))
      (node (ref "C54") (pin "2") (pinfunction "2_2") (pintype "passive"))
      (node (ref "C62") (pin "2") (pinfunction "2_2") (pintype "passive"))
      (node (ref "C68") (pin "2") (pinfunction "2_2") (pintype "passive"))
      (node (ref "C69") (pin "1") (pinfunction "1_1") (pintype "passive"))
      (node (ref "C70") (pin "1") (pinfunction "1_1") (pintype "passive"))
      (node (ref "C77") (pin "2") (pinfunction "2_2") (pintype "passive"))
      (node (ref "IC36") (pin "26") (pinfunction "DVSS2_26") (pintype "power_in"))
      (node (ref "IC36") (pin "43") (pinfunction "DVSS3_43") (pintype "power_in"))
      (node (ref "IC36") (pin "48") (pinfunction "AVSS2_48") (pintype "power_in"))
      (node (ref "IC36") (pin "49") (pinfunction "AVSS1_49") (pintype "power_in"))
      (node (ref "IC36") (pin "64") (pinfunction "AVSS3_64") (pintype "power_in"))
      (node (ref "IC36") (pin "65") (pinfunction "EP_65") (pintype "power_in"))
      (node (ref "IC36") (pin "8") (pinfunction "DVSS1_8") (pintype "power_in"))
      (node (ref "IC70") (pin "4") (pinfunction "GND_4") (pintype "power_in"))
      (node (ref "J19") (pin "6") (pinfunction "6_6") (pintype "bidirectional"))
      (node (ref "J8") (pin "5") (pinfunction "5_5") (pintype "bidirectional"))
      (node (ref "J8") (pin "7") (pinfunction "7_7") (pintype "bidirectional"))
      (node (ref "J8") (pin "9") (pinfunction "9_9") (pintype "bidirectional"))
      (node (ref "R110") (pin "1") (pinfunction "1_1") (pintype "passive"))
      (node (ref "R179") (pin "1") (pinfunction "1_1") (pintype "passive"))
      (node (ref "R238") (pin "1") (pinfunction "1_1") (pintype "passive"))
      (node (ref "R239") (pin "1") (pinfunction "1_1") (pintype "passive"))
      (node (ref "R257") (pin "1") (pinfunction "1_1") (pintype "passive"))
      (node (ref "R258") (pin "1") (pinfunction "1_1") (pintype "passive"))
      (node (ref "R259") (pin "1") (pinfunction "1_1") (pintype "passive"))
      (node (ref "R260") (pin "1") (pinfunction "1_1") (pintype "passive"))
      (node (ref "R261") (pin "1") (pinfunction "1_1") (pintype "passive"))
      (node (ref "R262") (pin "1") (pinfunction "1_1") (pintype "passive"))
      (node (ref "R263") (pin "1") (pinfunction "1_1") (pintype "passive"))
      (node (ref "R277") (pin "1") (pinfunction "1_1") (pintype "passive"))
      (node (ref "R278") (pin "1") (pinfunction "1_1") (pintype "passive"))
      (node (ref "R279") (pin "1") (pinfunction "1_1") (pintype "passive"))
      (node (ref "R280") (pin "1") (pinfunction "1_1") (pintype "passive"))
      (node (ref "R281") (pin "1") (pinfunction "1_1") (pintype "passive"))
      (node (ref "R93") (pin "2") (pinfunction "2_2") (pintype "passive"))
    )
    (net (code "44") (name "MGT_VCCAUX") (class "Default")
      (node (ref "R315") (pin "1") (pinfunction "1_1") (pintype "passive"))
    )
    (net (code "45") (name "Net-(IC36-BPCAP)") (class "Default")
      (node (ref "C69") (pin "2") (pinfunction "2_2") (pintype "passive"))
      (node (ref "C70") (pin "2") (pinfunction "2_2") (pintype "passive"))
      (node (ref "IC36") (pin "47") (pinfunction "BPCAP_47") (pintype "power_in"))
    )
    (net (code "46") (name "Net-(IC36-FPWM1{slash}GPIO5)") (class "Default")
      (node (ref "IC36") (pin "17") (pinfunction "FPWM1/GPIO5_17") (pintype "bidirectional"))
      (node (ref "R111") (pin "1") (pinfunction "1_1") (pintype "passive"))
    )
    (net (code "47") (name "Net-(IC36-FPWM2{slash}GPIO6)") (class "Default")
      (node (ref "IC36") (pin "18") (pinfunction "FPWM2/GPIO6_18") (pintype "bidirectional"))
      (node (ref "R181") (pin "1") (pinfunction "1_1") (pintype "passive"))
    )
    (net (code "48") (name "Net-(IC36-FPWM3{slash}GPIO7)") (class "Default")
      (node (ref "IC36") (pin "19") (pinfunction "FPWM3/GPIO7_19") (pintype "bidirectional"))
      (node (ref "R191") (pin "1") (pinfunction "1_1") (pintype "passive"))
    )
    (net (code "49") (name "Net-(IC36-FPWM4{slash}GPIO8)") (class "Default")
      (node (ref "IC36") (pin "20") (pinfunction "FPWM4/GPIO8_20") (pintype "bidirectional"))
      (node (ref "R226") (pin "1") (pinfunction "1_1") (pintype "passive"))
    )
    (net (code "50") (name "Net-(IC36-FPWM5{slash}GPIO9)") (class "Default")
      (node (ref "IC36") (pin "21") (pinfunction "FPWM5/GPIO9_21") (pintype "bidirectional"))
      (node (ref "R313") (pin "1") (pinfunction "1_1") (pintype "passive"))
    )
    (net (code "51") (name "Net-(IC36-FPWM6{slash}GPIO10)") (class "Default")
      (node (ref "IC36") (pin "22") (pinfunction "FPWM6/GPIO10_22") (pintype "bidirectional"))
      (node (ref "R314") (pin "1") (pinfunction "1_1") (pintype "passive"))
    )
    (net (code "52") (name "Net-(IC36-GPIO1)") (class "Default")
      (node (ref "IC36") (pin "11") (pinfunction "GPIO1_11") (pintype "bidirectional"))
      (node (ref "R94") (pin "1") (pinfunction "1_1") (pintype "passive"))
    )
    (net (code "53") (name "Net-(IC36-GPIO2)") (class "Default")
      (node (ref "IC36") (pin "12") (pinfunction "GPIO2_12") (pintype "bidirectional"))
      (node (ref "R95") (pin "1") (pinfunction "1_1") (pintype "passive"))
    )
    (net (code "54") (name "Net-(IC36-GPIO3)") (class "Default")
      (node (ref "IC36") (pin "13") (pinfunction "GPIO3_13") (pintype "bidirectional"))
      (node (ref "R96") (pin "1") (pinfunction "1_1") (pintype "passive"))
    )
    (net (code "55") (name "Net-(IC36-GPIO4)") (class "Default")
      (node (ref "IC36") (pin "14") (pinfunction "GPIO4_14") (pintype "bidirectional"))
      (node (ref "R99") (pin "1") (pinfunction "1_1") (pintype "passive"))
    )
    (net (code "56") (name "Net-(IC36-GPIO13)") (class "Default")
      (node (ref "IC36") (pin "25") (pinfunction "GPIO13_25") (pintype "bidirectional"))
      (node (ref "R101") (pin "1") (pinfunction "1_1") (pintype "passive"))
    )
    (net (code "57") (name "Net-(IC36-GPIO14)") (class "Default")
      (node (ref "IC36") (pin "29") (pinfunction "GPIO14_29") (pintype "bidirectional"))
      (node (ref "R103") (pin "1") (pinfunction "1_1") (pintype "passive"))
    )
    (net (code "58") (name "Net-(IC36-GPIO15)") (class "Default")
      (node (ref "IC36") (pin "30") (pinfunction "GPIO15_30") (pintype "bidirectional"))
      (node (ref "R105") (pin "1") (pinfunction "1_1") (pintype "passive"))
    )
    (net (code "59") (name "Net-(IC36-GPIO16)") (class "Default")
      (node (ref "IC36") (pin "33") (pinfunction "GPIO16_33") (pintype "bidirectional"))
      (node (ref "R107") (pin "1") (pinfunction "1_1") (pintype "passive"))
    )
    (net (code "60") (name "Net-(IC36-GPIO17)") (class "Default")
      (node (ref "IC36") (pin "34") (pinfunction "GPIO17_34") (pintype "bidirectional"))
      (node (ref "R108") (pin "1") (pinfunction "1_1") (pintype "passive"))
    )
    (net (code "61") (name "Net-(IC36-GPIO18)") (class "Default")
      (node (ref "IC36") (pin "35") (pinfunction "GPIO18_35") (pintype "bidirectional"))
      (node (ref "R109") (pin "1") (pinfunction "1_1") (pintype "passive"))
    )
    (net (code "62") (name "Net-(IC36-PMBUS_ADDR0)") (class "Default")
      (node (ref "IC36") (pin "61") (pinfunction "PMBUS_ADDR0_61") (pintype "input"))
      (node (ref "R110") (pin "2") (pinfunction "2_2") (pintype "passive"))
    )
    (net (code "63") (name "Net-(IC36-V33A)") (class "Default")
      (node (ref "IC36") (pin "46") (pinfunction "V33A_46") (pintype "power_in"))
      (node (ref "R112") (pin "2") (pinfunction "2_2") (pintype "passive"))
    )
    (net (code "64") (name "Net-(IC36-~{RESET})") (class "Default")
      (node (ref "C367") (pin "2") (pinfunction "2_2") (pintype "passive"))
      (node (ref "IC36") (pin "9") (pinfunction "~{RESET}_9") (pintype "input"))
      (node (ref "R227") (pin "1") (pinfunction "1_1") (pintype "passive"))
    )
    (net (code "65") (name "Net-(J19-Pad1)") (class "Default")
      (node (ref "J19") (pin "1") (pinfunction "1_1") (pintype "bidirectional"))
      (node (ref "R214") (pin "1") (pinfunction "1_1") (pintype "passive"))
    )
    (net (code "66") (name "P1V0VCCPAUX") (class "Default")
      (node (ref "R271") (pin "1") (pinfunction "1_1") (pintype "passive"))
    )
    (net (code "67") (name "P1V0_MGTAVCC") (class "Default")
      (node (ref "R264") (pin "1") (pinfunction "1_1") (pintype "passive"))
    )
    (net (code "68") (name "P1V0_VCCINT") (class "Default")
      (node (ref "R270") (pin "1") (pinfunction "1_1") (pintype "passive"))
    )
    (net (code "69") (name "P1V2_MGTAVTT") (class "Default")
      (node (ref "R267") (pin "1") (pinfunction "1_1") (pintype "passive"))
    )
    (net (code "70") (name "P1V8") (class "Default")
      (node (ref "C133") (pin "2") (pinfunction "2_2") (pintype "passive"))
      (node (ref "IC70") (pin "1") (pinfunction "VCCA_1") (pintype "power_in"))
      (node (ref "R265") (pin "2") (pinfunction "2_2") (pintype "passive"))
      (node (ref "R266") (pin "2") (pinfunction "2_2") (pintype "passive"))
      (node (ref "R269") (pin "1") (pinfunction "1_1") (pintype "passive"))
    )
    (net (code "71") (name "P2V5") (class "Default")
      (node (ref "R275") (pin "2") (pinfunction "2_2") (pintype "passive"))
    )
    (net (code "72") (name "P3V3") (class "Default")
      (node (ref "R276") (pin "2") (pinfunction "2_2") (pintype "passive"))
    )
    (net (code "73") (name "P3V3_REG") (class "Default")
      (node (ref "C134") (pin "2") (pinfunction "2_2") (pintype "passive"))
      (node (ref "C360") (pin "2") (pinfunction "2_2") (pintype "passive"))
      (node (ref "C362") (pin "2") (pinfunction "2_2") (pintype "passive"))
      (node (ref "C363") (pin "2") (pinfunction "2_2") (pintype "passive"))
      (node (ref "C368") (pin "2") (pinfunction "2_2") (pintype "passive"))
      (node (ref "C77") (pin "1") (pinfunction "1_1") (pintype "passive"))
      (node (ref "IC36") (pin "44") (pinfunction "V33DIO2_44") (pintype "power_in"))
      (node (ref "IC36") (pin "45") (pinfunction "V33D_45") (pintype "power_in"))
      (node (ref "IC36") (pin "7") (pinfunction "V33DIO1_7") (pintype "power_in"))
      (node (ref "IC70") (pin "8") (pinfunction "VCCB_8") (pintype "power_in"))
      (node (ref "J8") (pin "2") (pinfunction "2_2") (pintype "bidirectional"))
      (node (ref "R100") (pin "2") (pinfunction "2_2") (pintype "passive"))
      (node (ref "R102") (pin "2") (pinfunction "2_2") (pintype "passive"))
      (node (ref "R104") (pin "2") (pinfunction "2_2") (pintype "passive"))
      (node (ref "R106") (pin "2") (pinfunction "2_2") (pintype "passive"))
      (node (ref "R112") (pin "1") (pinfunction "1_1") (pintype "passive"))
      (node (ref "R113") (pin "2") (pinfunction "2_2") (pintype "passive"))
      (node (ref "R114") (pin "2") (pinfunction "2_2") (pintype "passive"))
      (node (ref "R116") (pin "2") (pinfunction "2_2") (pintype "passive"))
      (node (ref "R124") (pin "2") (pinfunction "2_2") (pintype "passive"))
      (node (ref "R127") (pin "2") (pinfunction "2_2") (pintype "passive"))
      (node (ref "R150") (pin "2") (pinfunction "2_2") (pintype "passive"))
      (node (ref "R152") (pin "2") (pinfunction "2_2") (pintype "passive"))
      (node (ref "R154") (pin "2") (pinfunction "2_2") (pintype "passive"))
      (node (ref "R177") (pin "2") (pinfunction "2_2") (pintype "passive"))
      (node (ref "R214") (pin "2") (pinfunction "2_2") (pintype "passive"))
      (node (ref "R227") (pin "2") (pinfunction "2_2") (pintype "passive"))
      (node (ref "R273") (pin "2") (pinfunction "2_2") (pintype "passive"))
      (node (ref "R89") (pin "2") (pinfunction "2_2") (pintype "passive"))
      (node (ref "R90") (pin "2") (pinfunction "2_2") (pintype "passive"))
      (node (ref "R91") (pin "2") (pinfunction "2_2") (pintype "passive"))
      (node (ref "R92") (pin "2") (pinfunction "2_2") (pintype "passive"))
    )
    (net (code "74") (name "P5V0_CLK") (class "Default")
      (node (ref "R272") (pin "2") (pinfunction "2_2") (pintype "passive"))
    )
    (net (code "75") (name "P12V0") (class "Default")
      (node (ref "R274") (pin "2") (pinfunction "2_2") (pintype "passive"))
    )
    (net (code "76") (name "VCCDDR") (class "Default")
      (node (ref "R268") (pin "1") (pinfunction "1_1") (pintype "passive"))
    )
    (net (code "77") (name "unconnected-(IC36-FPWM7{slash}GPIO11-Pad23)") (class "Default")
      (node (ref "IC36") (pin "23") (pinfunction "FPWM7/GPIO11_23") (pintype "bidirectional+no_connect"))
    )
    (net (code "78") (name "unconnected-(IC36-FPWM8{slash}GPIO12-Pad24)") (class "Default")
      (node (ref "IC36") (pin "24") (pinfunction "FPWM8/GPIO12_24") (pintype "bidirectional+no_connect"))
    )
    (net (code "79") (name "unconnected-(IC36-MON13-Pad56)") (class "Default")
      (node (ref "IC36") (pin "56") (pinfunction "MON13_56") (pintype "input+no_connect"))
    )
    (net (code "80") (name "unconnected-(IC36-NC1-Pad51)") (class "Default")
      (node (ref "IC36") (pin "51") (pinfunction "NC1_51") (pintype "output+no_connect"))
    )
    (net (code "81") (name "unconnected-(IC36-NC2-Pad53)") (class "Default")
      (node (ref "IC36") (pin "53") (pinfunction "NC2_53") (pintype "output+no_connect"))
    )
    (net (code "82") (name "unconnected-(IC36-NC3-Pad55)") (class "Default")
      (node (ref "IC36") (pin "55") (pinfunction "NC3_55") (pintype "power_in+no_connect"))
    )
    (net (code "83") (name "unconnected-(IC36-NC4-Pad57)") (class "Default")
      (node (ref "IC36") (pin "57") (pinfunction "NC4_57") (pintype "power_in+no_connect"))
    )
    (net (code "84") (name "unconnected-(IC36-PWM1{slash}GPI1-Pad31)") (class "Default")
      (node (ref "IC36") (pin "31") (pinfunction "PWM1/GPI1_31") (pintype "input+no_connect"))
    )
    (net (code "85") (name "unconnected-(IC36-PWM2{slash}GPI2-Pad32)") (class "Default")
      (node (ref "IC36") (pin "32") (pinfunction "PWM2/GPI2_32") (pintype "input+no_connect"))
    )
    (net (code "86") (name "unconnected-(IC36-PWM3{slash}GPI3-Pad42)") (class "Default")
      (node (ref "IC36") (pin "42") (pinfunction "PWM3/GPI3_42") (pintype "input+no_connect"))
    )
    (net (code "87") (name "unconnected-(IC36-PWM4{slash}GPI4-Pad41)") (class "Default")
      (node (ref "IC36") (pin "41") (pinfunction "PWM4/GPI4_41") (pintype "input+no_connect"))
    )
    (net (code "88") (name "unconnected-(IC36-TRCK-Pad10)") (class "Default")
      (node (ref "IC36") (pin "10") (pinfunction "TRCK_10") (pintype "output+no_connect"))
    )
    (net (code "89") (name "unconnected-(IC36-V33FB-Pad58)") (class "Default")
      (node (ref "IC36") (pin "58") (pinfunction "V33FB_58") (pintype "power_in+no_connect"))
    )
    (net (code "90") (name "unconnected-(IC70-EN-Pad5)") (class "Default")
      (node (ref "IC70") (pin "5") (pinfunction "EN_5") (pintype "input+no_connect"))
    )
    (net (code "91") (name "unconnected-(J19-Pad2)") (class "Default")
      (node (ref "J19") (pin "2") (pinfunction "2_2") (pintype "bidirectional+no_connect"))
    )
    (net (code "92") (name "unconnected-(J19-Pad3)") (class "Default")
      (node (ref "J19") (pin "3") (pinfunction "3_3") (pintype "bidirectional+no_connect"))
    )
    (net (code "93") (name "unconnected-(J19-Pad4)") (class "Default")
      (node (ref "J19") (pin "4") (pinfunction "4_4") (pintype "bidirectional+no_connect"))
    )
    (net (code "94") (name "unconnected-(J19-Pad5)") (class "Default")
      (node (ref "J19") (pin "5") (pinfunction "5_5") (pintype "bidirectional+no_connect"))
    )
  )
)
